# modular_expansion_basic_joystick_only.net
KiCad netlist of a schematic drawn in EAGLE
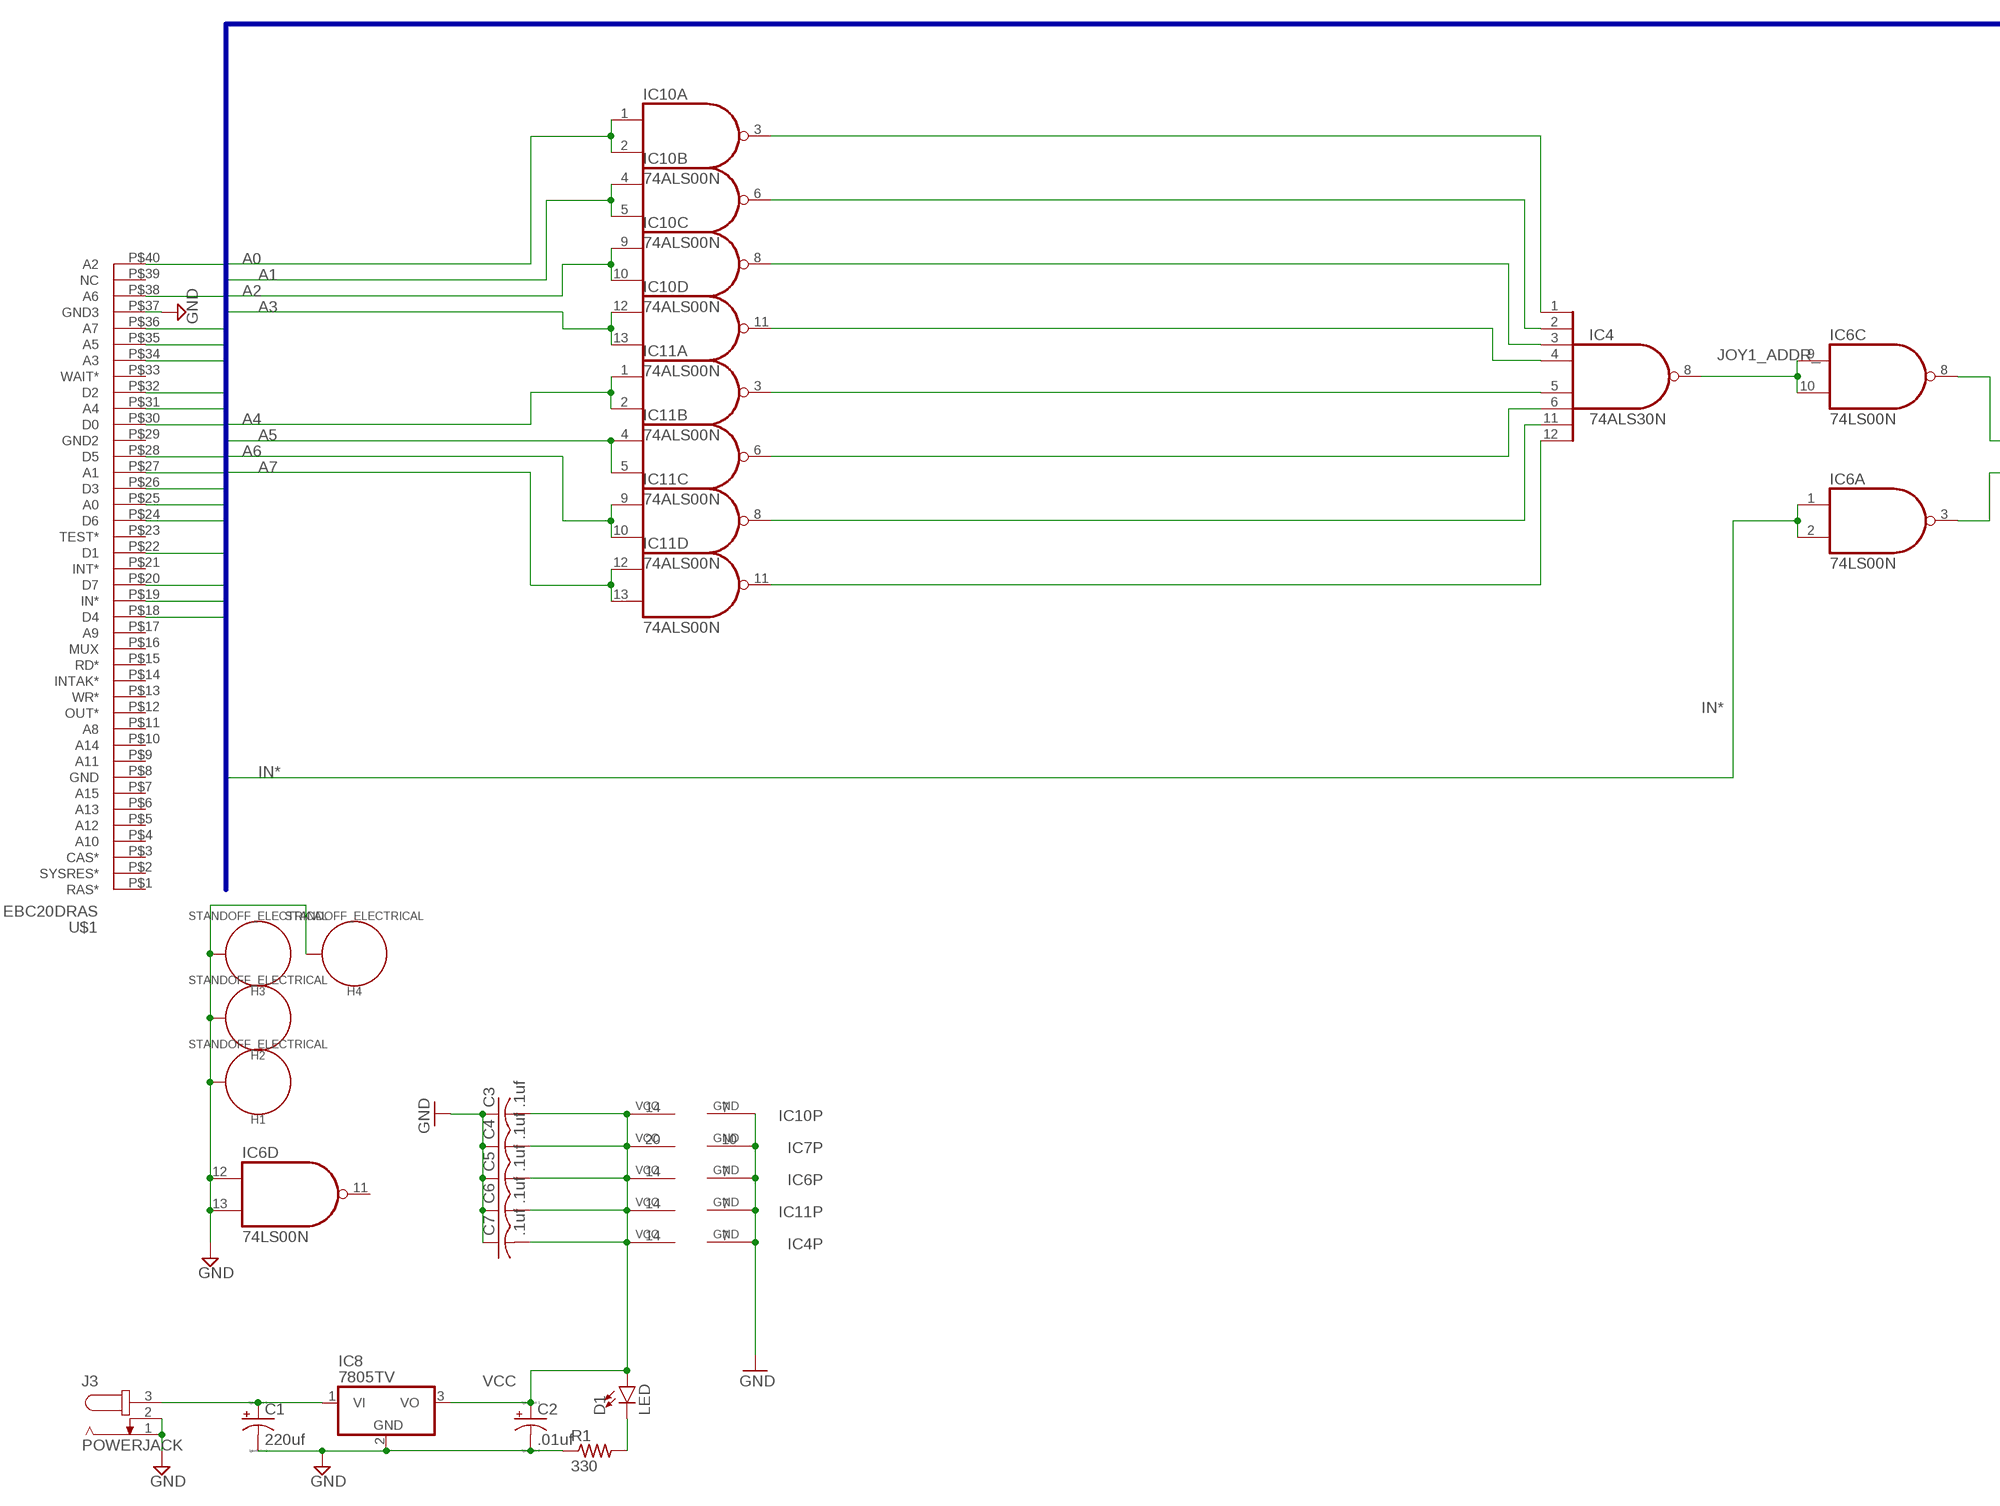
[diagram p0: schematic, sheet 1, part 1 of 2]
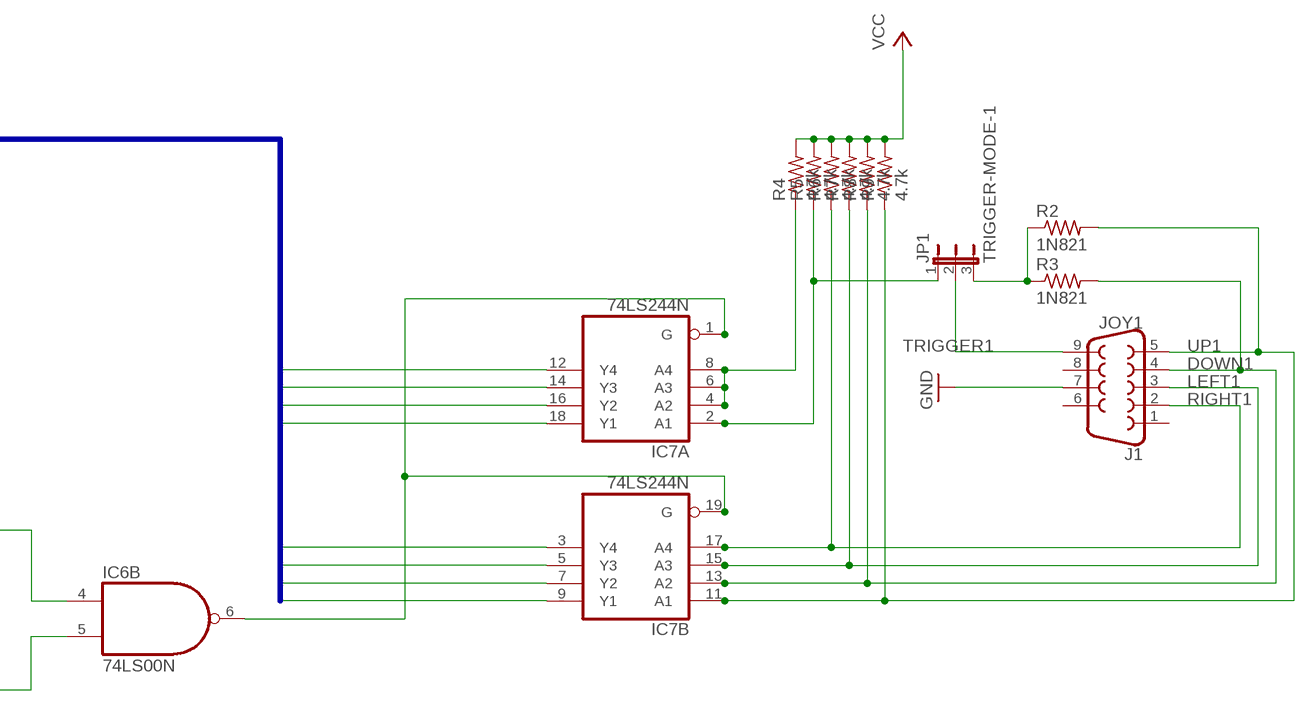
[diagram p1: schematic, sheet 1, part 2 of 2]

(export (version "E")
  (design (tool "Eeschema 10.0.6"))
  (components
    (comp (ref "C1")
      (value "220uf")
      (footprint "eagle-import:E3,5-10")
      (libsource (lib "eagle-import") (part "CPOL-USE3.5-10"))
    )
    (comp (ref "C2")
      (value ".01uf")
      (footprint "eagle-import:E2,5-6E")
      (libsource (lib "eagle-import") (part "CPOL-USE2,5-6E"))
    )
    (comp (ref "C3")
      (value ".1uf")
      (footprint "eagle-import:C025-025X050")
      (libsource (lib "eagle-import") (part "C-US025-025X050"))
    )
    (comp (ref "C4")
      (value ".1uf")
      (footprint "eagle-import:C025-025X050")
      (libsource (lib "eagle-import") (part "C-US025-025X050"))
    )
    (comp (ref "C5")
      (value ".1uf")
      (footprint "eagle-import:C025-025X050")
      (libsource (lib "eagle-import") (part "C-US025-025X050"))
    )
    (comp (ref "C6")
      (value ".1uf")
      (footprint "eagle-import:C025-025X050")
      (libsource (lib "eagle-import") (part "C-US025-025X050"))
    )
    (comp (ref "C7")
      (value ".1uf")
      (footprint "eagle-import:C025-025X050")
      (libsource (lib "eagle-import") (part "C-US025-025X050"))
    )
    (comp (ref "D1")
      (value "LED")
      (footprint "eagle-import:LED_3MM")
      (libsource (lib "eagle-import") (part "LED3MM"))
    )
    (comp (ref "H1")
      (value "STANDOFF_ELECTRICAL")
      (footprint "eagle-import:STANDOFF-ELECTRICAL")
      (libsource (lib "eagle-import") (part "STANDOFF_ELECTRICAL"))
    )
    (comp (ref "H2")
      (value "STANDOFF_ELECTRICAL")
      (footprint "eagle-import:STANDOFF-ELECTRICAL")
      (libsource (lib "eagle-import") (part "STANDOFF_ELECTRICAL"))
    )
    (comp (ref "H3")
      (value "STANDOFF_ELECTRICAL")
      (footprint "eagle-import:STANDOFF-ELECTRICAL")
      (libsource (lib "eagle-import") (part "STANDOFF_ELECTRICAL"))
    )
    (comp (ref "H4")
      (value "STANDOFF_ELECTRICAL")
      (footprint "eagle-import:STANDOFF-ELECTRICAL")
      (libsource (lib "eagle-import") (part "STANDOFF_ELECTRICAL"))
    )
    (comp (ref "IC4")
      (value "74ALS30N")
      (footprint "eagle-import:DIL14")
      (libsource (lib "eagle-import") (part "7430NALS"))
    )
    (comp (ref "IC6")
      (value "74LS00N")
      (footprint "eagle-import:DIL14")
      (libsource (lib "eagle-import") (part "7400NLS"))
    )
    (comp (ref "IC7")
      (value "74LS244N")
      (footprint "eagle-import:DIL20")
      (libsource (lib "eagle-import") (part "74244NLS"))
    )
    (comp (ref "IC8")
      (value "7805TV")
      (footprint "eagle-import:TO220V")
      (libsource (lib "eagle-import") (part "78TV05"))
    )
    (comp (ref "IC10")
      (value "74ALS00N")
      (footprint "eagle-import:DIL14")
      (libsource (lib "eagle-import") (part "7400NALS"))
    )
    (comp (ref "IC11")
      (value "74ALS00N")
      (footprint "eagle-import:DIL14")
      (libsource (lib "eagle-import") (part "7400NALS"))
    )
    (comp (ref "J1")
      (value "JOY1")
      (footprint "eagle-import:DB9")
      (libsource (lib "eagle-import") (part "DB9FEMALE"))
    )
    (comp (ref "J3")
      (value "POWERJACK")
      (footprint "eagle-import:SPC4077")
      (libsource (lib "eagle-import") (part "JACK-PLUG0"))
    )
    (comp (ref "JP1")
      (value "TRIGGER-MODE-1")
      (footprint "eagle-import:JP2")
      (libsource (lib "eagle-import") (part "JP2E"))
    )
    (comp (ref "R1")
      (value "330")
      (footprint "eagle-import:0204V")
      (libsource (lib "eagle-import") (part "resistor_348_R-US_0204/2V"))
    )
    (comp (ref "R2")
      (value "1N821")
      (footprint "eagle-import:0204V")
      (libsource (lib "eagle-import") (part "R-US_0204/2V"))
    )
    (comp (ref "R3")
      (value "1N821")
      (footprint "eagle-import:0204V")
      (libsource (lib "eagle-import") (part "R-US_0204/2V"))
    )
    (comp (ref "R4")
      (value "4.7k")
      (footprint "eagle-import:0204_5")
      (libsource (lib "eagle-import") (part "R-US_0204/5"))
    )
    (comp (ref "R5")
      (value "4.7k")
      (footprint "eagle-import:0204_5")
      (libsource (lib "eagle-import") (part "R-US_0204/5"))
    )
    (comp (ref "R6")
      (value "4.7k")
      (footprint "eagle-import:0204_5")
      (libsource (lib "eagle-import") (part "R-US_0204/5"))
    )
    (comp (ref "R7")
      (value "4.7k")
      (footprint "eagle-import:0204_5")
      (libsource (lib "eagle-import") (part "R-US_0204/5"))
    )
    (comp (ref "R8")
      (value "4.7k")
      (footprint "eagle-import:0204_5")
      (libsource (lib "eagle-import") (part "R-US_0204/5"))
    )
    (comp (ref "R9")
      (value "4.7k")
      (footprint "eagle-import:0204_5")
      (libsource (lib "eagle-import") (part "R-US_0204/5"))
    )
    (comp (ref "U$1")
      (value "EBC20DRAS")
      (footprint "eagle-import:EBC20DRAS")
      (libsource (lib "eagle-import") (part "EBC20DRAS"))
    )
  )
  (nets
    (net (code "1") (name "/A0") (class "Default")
      (node (ref "IC10") (pin "1") (pinfunction "I0_1") (pintype "input"))
      (node (ref "IC10") (pin "2") (pinfunction "I1_2") (pintype "input"))
      (node (ref "U$1") (pin "P$25") (pinfunction "A0_P$25") (pintype "bidirectional"))
    )
    (net (code "2") (name "/A1") (class "Default")
      (node (ref "IC10") (pin "4") (pinfunction "I0_4") (pintype "input"))
      (node (ref "IC10") (pin "5") (pinfunction "I1_5") (pintype "input"))
      (node (ref "U$1") (pin "P$27") (pinfunction "A1_P$27") (pintype "bidirectional"))
    )
    (net (code "3") (name "/A2") (class "Default")
      (node (ref "IC10") (pin "10") (pinfunction "I1_10") (pintype "input"))
      (node (ref "IC10") (pin "9") (pinfunction "I0_9") (pintype "input"))
      (node (ref "U$1") (pin "P$40") (pinfunction "A2_P$40") (pintype "bidirectional"))
    )
    (net (code "4") (name "/A3") (class "Default")
      (node (ref "IC10") (pin "12") (pinfunction "I0_12") (pintype "input"))
      (node (ref "IC10") (pin "13") (pinfunction "I1_13") (pintype "input"))
      (node (ref "U$1") (pin "P$34") (pinfunction "A3_P$34") (pintype "bidirectional"))
    )
    (net (code "5") (name "/A4") (class "Default")
      (node (ref "IC11") (pin "1") (pinfunction "I0_1") (pintype "input"))
      (node (ref "IC11") (pin "2") (pinfunction "I1_2") (pintype "input"))
      (node (ref "U$1") (pin "P$31") (pinfunction "A4_P$31") (pintype "bidirectional"))
    )
    (net (code "6") (name "/A5") (class "Default")
      (node (ref "IC11") (pin "4") (pinfunction "I0_4") (pintype "input"))
      (node (ref "IC11") (pin "5") (pinfunction "I1_5") (pintype "input"))
      (node (ref "U$1") (pin "P$35") (pinfunction "A5_P$35") (pintype "bidirectional"))
    )
    (net (code "7") (name "/A6") (class "Default")
      (node (ref "IC11") (pin "10") (pinfunction "I1_10") (pintype "input"))
      (node (ref "IC11") (pin "9") (pinfunction "I0_9") (pintype "input"))
      (node (ref "U$1") (pin "P$38") (pinfunction "A6_P$38") (pintype "bidirectional"))
    )
    (net (code "8") (name "/A7") (class "Default")
      (node (ref "IC11") (pin "12") (pinfunction "I0_12") (pintype "input"))
      (node (ref "IC11") (pin "13") (pinfunction "I1_13") (pintype "input"))
      (node (ref "U$1") (pin "P$36") (pinfunction "A7_P$36") (pintype "bidirectional"))
    )
    (net (code "9") (name "/D0") (class "Default")
      (node (ref "IC7") (pin "9") (pinfunction "Y1_9") (pintype "tri_state"))
      (node (ref "U$1") (pin "P$30") (pinfunction "D0_P$30") (pintype "bidirectional"))
    )
    (net (code "10") (name "/D1") (class "Default")
      (node (ref "IC7") (pin "7") (pinfunction "Y2_7") (pintype "tri_state"))
      (node (ref "U$1") (pin "P$22") (pinfunction "D1_P$22") (pintype "bidirectional"))
    )
    (net (code "11") (name "/D2") (class "Default")
      (node (ref "IC7") (pin "5") (pinfunction "Y3_5") (pintype "tri_state"))
      (node (ref "U$1") (pin "P$32") (pinfunction "D2_P$32") (pintype "bidirectional"))
    )
    (net (code "12") (name "/D3") (class "Default")
      (node (ref "IC7") (pin "3") (pinfunction "Y4_3") (pintype "tri_state"))
      (node (ref "U$1") (pin "P$26") (pinfunction "D3_P$26") (pintype "bidirectional"))
    )
    (net (code "13") (name "/D4") (class "Default")
      (node (ref "IC7") (pin "18") (pinfunction "Y1_18") (pintype "tri_state"))
      (node (ref "U$1") (pin "P$18") (pinfunction "D4_P$18") (pintype "bidirectional"))
    )
    (net (code "14") (name "/D5") (class "Default")
      (node (ref "IC7") (pin "16") (pinfunction "Y2_16") (pintype "tri_state"))
      (node (ref "U$1") (pin "P$28") (pinfunction "D5_P$28") (pintype "bidirectional"))
    )
    (net (code "15") (name "/D6") (class "Default")
      (node (ref "IC7") (pin "14") (pinfunction "Y3_14") (pintype "tri_state"))
      (node (ref "U$1") (pin "P$24") (pinfunction "D6_P$24") (pintype "bidirectional"))
    )
    (net (code "16") (name "/D7") (class "Default")
      (node (ref "IC7") (pin "12") (pinfunction "Y4_12") (pintype "tri_state"))
      (node (ref "U$1") (pin "P$20") (pinfunction "D7_P$20") (pintype "bidirectional"))
    )
    (net (code "17") (name "/DOWN1") (class "Default")
      (node (ref "IC7") (pin "13") (pinfunction "A2_13") (pintype "input"))
      (node (ref "J1") (pin "4") (pinfunction "4_4") (pintype "passive"))
      (node (ref "R3") (pin "2") (pinfunction "2_2") (pintype "passive"))
      (node (ref "R8") (pin "1") (pinfunction "1_1") (pintype "passive"))
    )
    (net (code "18") (name "/IN*") (class "Default")
      (node (ref "IC6") (pin "1") (pinfunction "I0_1") (pintype "input"))
      (node (ref "IC6") (pin "2") (pinfunction "I1_2") (pintype "input"))
      (node (ref "U$1") (pin "P$19") (pinfunction "IN*_P$19") (pintype "bidirectional"))
    )
    (net (code "19") (name "/JOY1_ADDR_") (class "Default")
      (node (ref "IC4") (pin "8") (pinfunction "O_8") (pintype "output"))
      (node (ref "IC6") (pin "10") (pinfunction "I1_10") (pintype "input"))
      (node (ref "IC6") (pin "9") (pinfunction "I0_9") (pintype "input"))
    )
    (net (code "20") (name "/LEFT1") (class "Default")
      (node (ref "IC7") (pin "15") (pinfunction "A3_15") (pintype "input"))
      (node (ref "J1") (pin "3") (pinfunction "3_3") (pintype "passive"))
      (node (ref "R7") (pin "1") (pinfunction "1_1") (pintype "passive"))
    )
    (net (code "21") (name "/RIGHT1") (class "Default")
      (node (ref "IC7") (pin "17") (pinfunction "A4_17") (pintype "input"))
      (node (ref "J1") (pin "2") (pinfunction "2_2") (pintype "passive"))
      (node (ref "R6") (pin "1") (pinfunction "1_1") (pintype "passive"))
    )
    (net (code "22") (name "/TRIGGER1") (class "Default")
      (node (ref "J1") (pin "9") (pinfunction "9_9") (pintype "passive"))
      (node (ref "JP1") (pin "2") (pinfunction "2_2") (pintype "passive"))
    )
    (net (code "23") (name "/UP1") (class "Default")
      (node (ref "IC7") (pin "11") (pinfunction "A1_11") (pintype "input"))
      (node (ref "J1") (pin "5") (pinfunction "5_5") (pintype "passive"))
      (node (ref "R2") (pin "2") (pinfunction "2_2") (pintype "passive"))
      (node (ref "R9") (pin "1") (pinfunction "1_1") (pintype "passive"))
    )
    (net (code "24") (name "GND") (class "Default")
      (node (ref "C1") (pin "-") (pinfunction "-_-") (pintype "passive"))
      (node (ref "C2") (pin "-") (pinfunction "-_-") (pintype "passive"))
      (node (ref "C3") (pin "1") (pinfunction "1_1") (pintype "passive"))
      (node (ref "C4") (pin "1") (pinfunction "1_1") (pintype "passive"))
      (node (ref "C5") (pin "1") (pinfunction "1_1") (pintype "passive"))
      (node (ref "C6") (pin "1") (pinfunction "1_1") (pintype "passive"))
      (node (ref "C7") (pin "1") (pinfunction "1_1") (pintype "passive"))
      (node (ref "H1") (pin "P1") (pinfunction "P$1_P1") (pintype "bidirectional"))
      (node (ref "H2") (pin "P1") (pinfunction "P$1_P1") (pintype "bidirectional"))
      (node (ref "H3") (pin "P1") (pinfunction "P$1_P1") (pintype "bidirectional"))
      (node (ref "H4") (pin "P1") (pinfunction "P$1_P1") (pintype "bidirectional"))
      (node (ref "IC10") (pin "7") (pinfunction "GND_7") (pintype "power_in"))
      (node (ref "IC11") (pin "7") (pinfunction "GND_7") (pintype "power_in"))
      (node (ref "IC4") (pin "7") (pinfunction "GND_7") (pintype "power_in"))
      (node (ref "IC6") (pin "12") (pinfunction "I0_12") (pintype "input"))
      (node (ref "IC6") (pin "13") (pinfunction "I1_13") (pintype "input"))
      (node (ref "IC6") (pin "7") (pinfunction "GND_7") (pintype "power_in"))
      (node (ref "IC7") (pin "10") (pinfunction "GND_10") (pintype "power_in"))
      (node (ref "IC8") (pin "2") (pinfunction "GND_2") (pintype "passive"))
      (node (ref "J1") (pin "7") (pinfunction "7_7") (pintype "passive"))
      (node (ref "J3") (pin "1") (pinfunction "1_1") (pintype "passive"))
      (node (ref "J3") (pin "2") (pinfunction "2_2") (pintype "passive"))
      (node (ref "R1") (pin "1") (pinfunction "1_1") (pintype "passive"))
      (node (ref "U$1") (pin "P$37") (pinfunction "GND3_P$37") (pintype "bidirectional"))
    )
    (net (code "25") (name "Net-(D1-C)") (class "Default")
      (node (ref "D1") (pin "K") (pinfunction "C_K") (pintype "passive"))
      (node (ref "R1") (pin "2") (pinfunction "2_2") (pintype "passive"))
    )
    (net (code "26") (name "Net-(IC6A-O)") (class "Default")
      (node (ref "IC6") (pin "3") (pinfunction "O_3") (pintype "output"))
      (node (ref "IC6") (pin "5") (pinfunction "I1_5") (pintype "input"))
    )
    (net (code "27") (name "Net-(IC6B-I0)") (class "Default")
      (node (ref "IC6") (pin "4") (pinfunction "I0_4") (pintype "input"))
      (node (ref "IC6") (pin "8") (pinfunction "O_8") (pintype "output"))
    )
    (net (code "28") (name "Net-(IC6B-O)") (class "Default")
      (node (ref "IC6") (pin "6") (pinfunction "O_6") (pintype "output"))
      (node (ref "IC7") (pin "1") (pinfunction "G_1") (pintype "input"))
      (node (ref "IC7") (pin "19") (pinfunction "G_19") (pintype "input"))
    )
    (net (code "29") (name "Net-(IC7A-A1)") (class "Default")
      (node (ref "IC7") (pin "2") (pinfunction "A1_2") (pintype "input"))
      (node (ref "JP1") (pin "1") (pinfunction "1_1") (pintype "passive"))
      (node (ref "R5") (pin "1") (pinfunction "1_1") (pintype "passive"))
    )
    (net (code "30") (name "Net-(IC7A-A2)") (class "Default")
      (node (ref "IC7") (pin "4") (pinfunction "A2_4") (pintype "input"))
      (node (ref "IC7") (pin "6") (pinfunction "A3_6") (pintype "input"))
      (node (ref "IC7") (pin "8") (pinfunction "A4_8") (pintype "input"))
      (node (ref "R4") (pin "1") (pinfunction "1_1") (pintype "passive"))
    )
    (net (code "31") (name "Net-(IC8-VI)") (class "Default")
      (node (ref "C1") (pin "+") (pinfunction "+_+") (pintype "passive"))
      (node (ref "IC8") (pin "1") (pinfunction "VI_1") (pintype "input"))
      (node (ref "J3") (pin "3") (pinfunction "3_3") (pintype "passive"))
    )
    (net (code "32") (name "Net-(IC10A-O)") (class "Default")
      (node (ref "IC10") (pin "3") (pinfunction "O_3") (pintype "output"))
      (node (ref "IC4") (pin "1") (pinfunction "I0_1") (pintype "input"))
    )
    (net (code "33") (name "Net-(IC10B-O)") (class "Default")
      (node (ref "IC10") (pin "6") (pinfunction "O_6") (pintype "output"))
      (node (ref "IC4") (pin "2") (pinfunction "I1_2") (pintype "input"))
    )
    (net (code "34") (name "Net-(IC10C-O)") (class "Default")
      (node (ref "IC10") (pin "8") (pinfunction "O_8") (pintype "output"))
      (node (ref "IC4") (pin "3") (pinfunction "I2_3") (pintype "input"))
    )
    (net (code "35") (name "Net-(IC10D-O)") (class "Default")
      (node (ref "IC10") (pin "11") (pinfunction "O_11") (pintype "output"))
      (node (ref "IC4") (pin "4") (pinfunction "I3_4") (pintype "input"))
    )
    (net (code "36") (name "Net-(IC11A-O)") (class "Default")
      (node (ref "IC11") (pin "3") (pinfunction "O_3") (pintype "output"))
      (node (ref "IC4") (pin "5") (pinfunction "I4_5") (pintype "input"))
    )
    (net (code "37") (name "Net-(IC11B-O)") (class "Default")
      (node (ref "IC11") (pin "6") (pinfunction "O_6") (pintype "output"))
      (node (ref "IC4") (pin "6") (pinfunction "I5_6") (pintype "input"))
    )
    (net (code "38") (name "Net-(IC11C-O)") (class "Default")
      (node (ref "IC11") (pin "8") (pinfunction "O_8") (pintype "output"))
      (node (ref "IC4") (pin "11") (pinfunction "I6_11") (pintype "input"))
    )
    (net (code "39") (name "Net-(IC11D-O)") (class "Default")
      (node (ref "IC11") (pin "11") (pinfunction "O_11") (pintype "output"))
      (node (ref "IC4") (pin "12") (pinfunction "I7_12") (pintype "input"))
    )
    (net (code "40") (name "Net-(JP1-Pad3)") (class "Default")
      (node (ref "JP1") (pin "3") (pinfunction "3_3") (pintype "passive"))
      (node (ref "R2") (pin "1") (pinfunction "1_1") (pintype "passive"))
      (node (ref "R3") (pin "1") (pinfunction "1_1") (pintype "passive"))
    )
    (net (code "41") (name "VCC") (class "Default")
      (node (ref "C2") (pin "+") (pinfunction "+_+") (pintype "passive"))
      (node (ref "C3") (pin "2") (pinfunction "2_2") (pintype "passive"))
      (node (ref "C4") (pin "2") (pinfunction "2_2") (pintype "passive"))
      (node (ref "C5") (pin "2") (pinfunction "2_2") (pintype "passive"))
      (node (ref "C6") (pin "2") (pinfunction "2_2") (pintype "passive"))
      (node (ref "C7") (pin "2") (pinfunction "2_2") (pintype "passive"))
      (node (ref "D1") (pin "A") (pinfunction "A_A") (pintype "passive"))
      (node (ref "IC10") (pin "14") (pinfunction "VCC_14") (pintype "power_in"))
      (node (ref "IC11") (pin "14") (pinfunction "VCC_14") (pintype "power_in"))
      (node (ref "IC4") (pin "14") (pinfunction "VCC_14") (pintype "power_in"))
      (node (ref "IC6") (pin "14") (pinfunction "VCC_14") (pintype "power_in"))
      (node (ref "IC7") (pin "20") (pinfunction "VCC_20") (pintype "power_in"))
      (node (ref "IC8") (pin "3") (pinfunction "VO_3") (pintype "passive"))
      (node (ref "R4") (pin "2") (pinfunction "2_2") (pintype "passive"))
      (node (ref "R5") (pin "2") (pinfunction "2_2") (pintype "passive"))
      (node (ref "R6") (pin "2") (pinfunction "2_2") (pintype "passive"))
      (node (ref "R7") (pin "2") (pinfunction "2_2") (pintype "passive"))
      (node (ref "R8") (pin "2") (pinfunction "2_2") (pintype "passive"))
      (node (ref "R9") (pin "2") (pinfunction "2_2") (pintype "passive"))
    )
    (net (code "42") (name "unconnected-(IC6D-O-Pad11)") (class "Default")
      (node (ref "IC6") (pin "11") (pinfunction "O_11") (pintype "output"))
    )
    (net (code "43") (name "unconnected-(J1-Pad1)") (class "Default")
      (node (ref "J1") (pin "1") (pinfunction "1_1") (pintype "passive"))
    )
    (net (code "44") (name "unconnected-(J1-Pad6)") (class "Default")
      (node (ref "J1") (pin "6") (pinfunction "6_6") (pintype "passive"))
    )
    (net (code "45") (name "unconnected-(J1-Pad8)") (class "Default")
      (node (ref "J1") (pin "8") (pinfunction "8_8") (pintype "passive"))
    )
    (net (code "46") (name "unconnected-(U$1-A8-PadP$11)") (class "Default")
      (node (ref "U$1") (pin "P$11") (pinfunction "A8_P$11") (pintype "bidirectional"))
    )
    (net (code "47") (name "unconnected-(U$1-A9-PadP$17)") (class "Default")
      (node (ref "U$1") (pin "P$17") (pinfunction "A9_P$17") (pintype "bidirectional"))
    )
    (net (code "48") (name "unconnected-(U$1-A10-PadP$4)") (class "Default")
      (node (ref "U$1") (pin "P$4") (pinfunction "A10_P$4") (pintype "bidirectional"))
    )
    (net (code "49") (name "unconnected-(U$1-A11-PadP$9)") (class "Default")
      (node (ref "U$1") (pin "P$9") (pinfunction "A11_P$9") (pintype "bidirectional"))
    )
    (net (code "50") (name "unconnected-(U$1-A12-PadP$5)") (class "Default")
      (node (ref "U$1") (pin "P$5") (pinfunction "A12_P$5") (pintype "bidirectional"))
    )
    (net (code "51") (name "unconnected-(U$1-A13-PadP$6)") (class "Default")
      (node (ref "U$1") (pin "P$6") (pinfunction "A13_P$6") (pintype "bidirectional"))
    )
    (net (code "52") (name "unconnected-(U$1-A14-PadP$10)") (class "Default")
      (node (ref "U$1") (pin "P$10") (pinfunction "A14_P$10") (pintype "bidirectional"))
    )
    (net (code "53") (name "unconnected-(U$1-A15-PadP$7)") (class "Default")
      (node (ref "U$1") (pin "P$7") (pinfunction "A15_P$7") (pintype "bidirectional"))
    )
    (net (code "54") (name "unconnected-(U$1-CAS*-PadP$3)") (class "Default")
      (node (ref "U$1") (pin "P$3") (pinfunction "CAS*_P$3") (pintype "bidirectional"))
    )
    (net (code "55") (name "unconnected-(U$1-GND-PadP$8)") (class "Default")
      (node (ref "U$1") (pin "P$8") (pinfunction "GND_P$8") (pintype "bidirectional"))
    )
    (net (code "56") (name "unconnected-(U$1-GND2-PadP$29)") (class "Default")
      (node (ref "U$1") (pin "P$29") (pinfunction "GND2_P$29") (pintype "bidirectional"))
    )
    (net (code "57") (name "unconnected-(U$1-INT*-PadP$21)") (class "Default")
      (node (ref "U$1") (pin "P$21") (pinfunction "INT*_P$21") (pintype "bidirectional"))
    )
    (net (code "58") (name "unconnected-(U$1-INTAK*-PadP$14)") (class "Default")
      (node (ref "U$1") (pin "P$14") (pinfunction "INTAK*_P$14") (pintype "bidirectional"))
    )
    (net (code "59") (name "unconnected-(U$1-MUX-PadP$16)") (class "Default")
      (node (ref "U$1") (pin "P$16") (pinfunction "MUX_P$16") (pintype "bidirectional"))
    )
    (net (code "60") (name "unconnected-(U$1-NC-PadP$39)") (class "Default")
      (node (ref "U$1") (pin "P$39") (pinfunction "NC_P$39") (pintype "bidirectional"))
    )
    (net (code "61") (name "unconnected-(U$1-OUT*-PadP$12)") (class "Default")
      (node (ref "U$1") (pin "P$12") (pinfunction "OUT*_P$12") (pintype "bidirectional"))
    )
    (net (code "62") (name "unconnected-(U$1-RAS*-PadP$1)") (class "Default")
      (node (ref "U$1") (pin "P$1") (pinfunction "RAS*_P$1") (pintype "bidirectional"))
    )
    (net (code "63") (name "unconnected-(U$1-RD*-PadP$15)") (class "Default")
      (node (ref "U$1") (pin "P$15") (pinfunction "RD*_P$15") (pintype "bidirectional"))
    )
    (net (code "64") (name "unconnected-(U$1-SYSRES*-PadP$2)") (class "Default")
      (node (ref "U$1") (pin "P$2") (pinfunction "SYSRES*_P$2") (pintype "bidirectional"))
    )
    (net (code "65") (name "unconnected-(U$1-TEST*-PadP$23)") (class "Default")
      (node (ref "U$1") (pin "P$23") (pinfunction "TEST*_P$23") (pintype "bidirectional"))
    )
    (net (code "66") (name "unconnected-(U$1-WAIT*-PadP$33)") (class "Default")
      (node (ref "U$1") (pin "P$33") (pinfunction "WAIT*_P$33") (pintype "bidirectional"))
    )
    (net (code "67") (name "unconnected-(U$1-WR*-PadP$13)") (class "Default")
      (node (ref "U$1") (pin "P$13") (pinfunction "WR*_P$13") (pintype "bidirectional"))
    )
  )
)
